# DEMO.net
KiCad netlist of a schematic drawn in Altium Designer
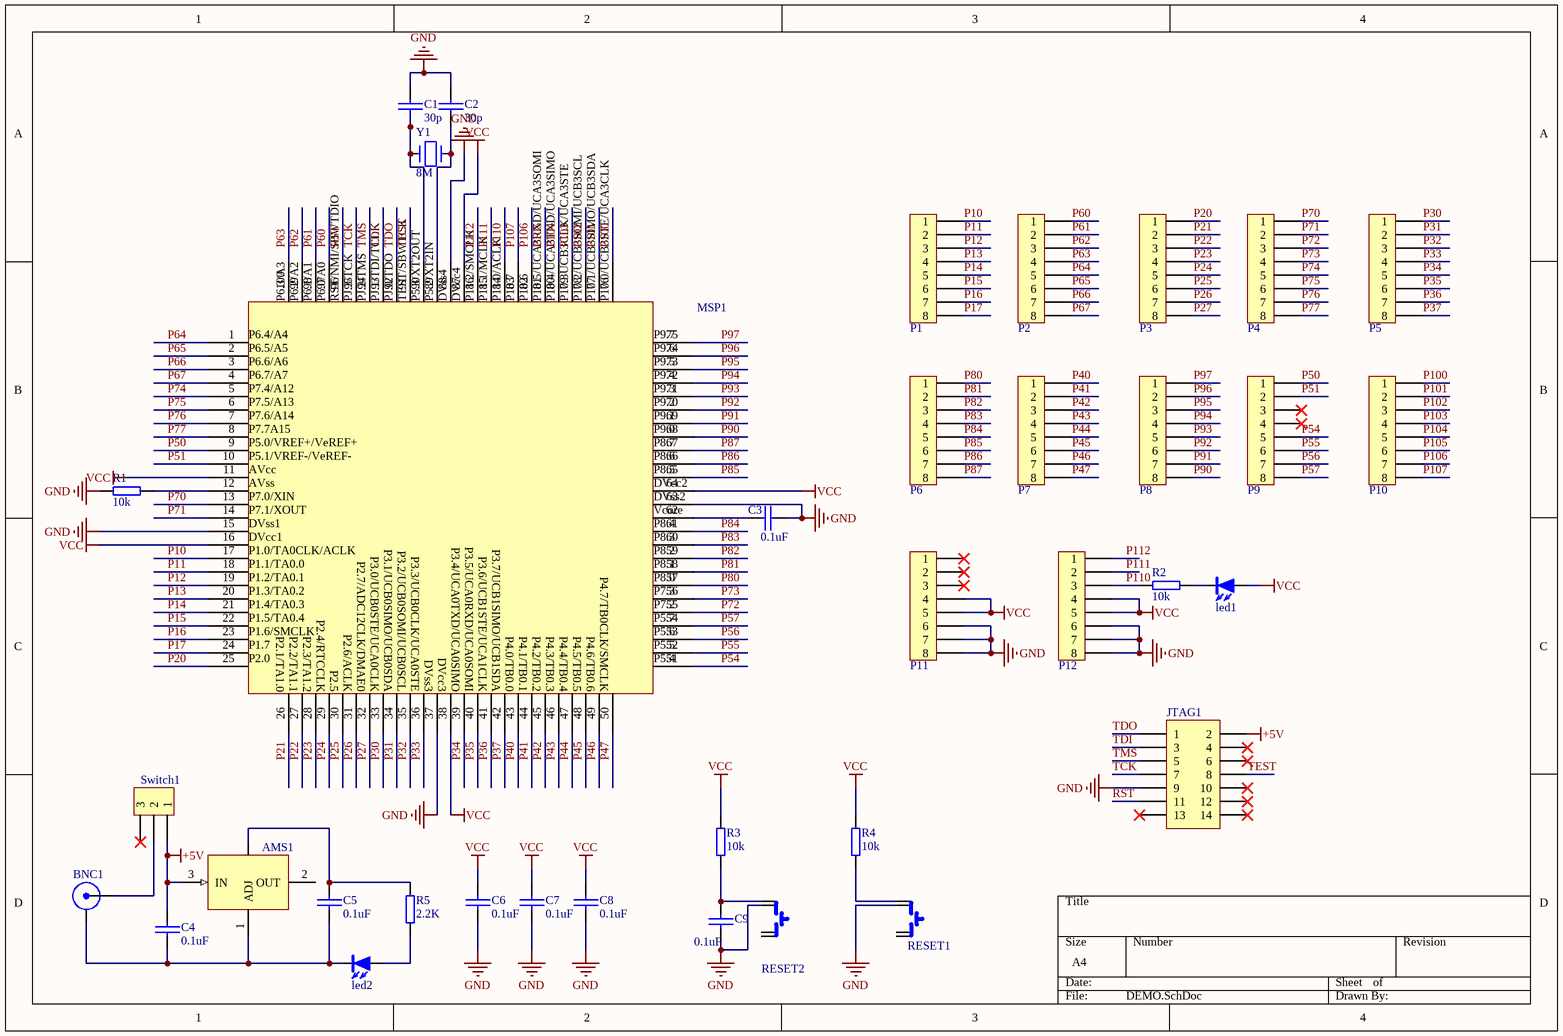
[diagram p0: DEMO.SchDoc]

(export (version "E")
  (design (tool "Eeschema 10.0.6"))
  (components
    (comp (ref "AMS1")
      (value "1117")
      (footprint "SOT-223/P2.3")
      (libsource (lib "MSP430F5438A") (part "1117"))
    )
    (comp (ref "BNC1") (value "BNC") (footprint "POWER0") (libsource (lib "MSP430F5438A") (part "BNC")))
    (comp (ref "C1") (value "30p") (footprint "0805") (libsource (lib "MSP430F5438A") (part "C1")))
    (comp (ref "C2") (value "30p") (footprint "0805") (libsource (lib "MSP430F5438A") (part "C1")))
    (comp (ref "C3") (value "0.1uF") (footprint "0805") (libsource (lib "MSP430F5438A") (part "C1")))
    (comp (ref "C4") (value "0.1uF") (footprint "0805") (libsource (lib "MSP430F5438A") (part "C1")))
    (comp (ref "C5") (value "0.1uF") (footprint "0805") (libsource (lib "MSP430F5438A") (part "C1")))
    (comp (ref "C6") (value "0.1uF") (footprint "0805") (libsource (lib "MSP430F5438A") (part "C1")))
    (comp (ref "C7") (value "0.1uF") (footprint "0805") (libsource (lib "MSP430F5438A") (part "C1")))
    (comp (ref "C8") (value "0.1uF") (footprint "0805") (libsource (lib "MSP430F5438A") (part "C1")))
    (comp (ref "C9") (value "0.1uF") (footprint "0805") (libsource (lib "MSP430F5438A") (part "C1")))
    (comp (ref "JTAG1")
      (value "Header 7X2")
      (footprint "IDC14A")
      (description "Header, 7-Pin, Dual row")
      (fields (field (name "PUBLISHER") "Altium Limited"))
      (libsource (lib "MSP430F5438A") (part "Header 7X2"))
    )
    (comp (ref "led1") (value "LED2") (footprint "0805") (libsource (lib "MSP430F5438A") (part "LED2")))
    (comp (ref "led2") (value "LED2") (footprint "0805") (libsource (lib "MSP430F5438A") (part "LED2")))
    (comp (ref "MSP1")
      (value "MSP430F5438")
      (footprint "TQFP100")
      (libsource (lib "MSP430F5438A") (part "MSP430F5438"))
    )
    (comp (ref "P1") (value "CON8") (footprint "SIP8") (libsource (lib "MSP430F5438A") (part "CON8")))
    (comp (ref "P2") (value "CON8") (footprint "SIP8") (libsource (lib "MSP430F5438A") (part "CON8")))
    (comp (ref "P3") (value "CON8") (footprint "SIP8") (libsource (lib "MSP430F5438A") (part "CON8")))
    (comp (ref "P4") (value "CON8") (footprint "SIP8") (libsource (lib "MSP430F5438A") (part "CON8")))
    (comp (ref "P5") (value "CON8") (footprint "SIP8") (libsource (lib "MSP430F5438A") (part "CON8")))
    (comp (ref "P6") (value "CON8") (footprint "SIP8") (libsource (lib "MSP430F5438A") (part "CON8")))
    (comp (ref "P7") (value "CON8") (footprint "SIP8") (libsource (lib "MSP430F5438A") (part "CON8")))
    (comp (ref "P8") (value "CON8") (footprint "SIP8") (libsource (lib "MSP430F5438A") (part "CON8")))
    (comp (ref "P9") (value "CON8") (footprint "SIP8") (libsource (lib "MSP430F5438A") (part "CON8")))
    (comp (ref "P10") (value "CON8") (footprint "SIP8") (libsource (lib "MSP430F5438A") (part "CON8")))
    (comp (ref "P11") (value "CON8") (footprint "SIP8") (libsource (lib "MSP430F5438A") (part "CON8")))
    (comp (ref "P12") (value "CON8") (footprint "SIP8") (libsource (lib "MSP430F5438A") (part "CON8")))
    (comp (ref "R1") (value "10k") (footprint "0805") (libsource (lib "MSP430F5438A") (part "R1")))
    (comp (ref "R2") (value "10k") (footprint "0805") (libsource (lib "MSP430F5438A") (part "R1")))
    (comp (ref "R3") (value "10k") (footprint "0805") (libsource (lib "MSP430F5438A") (part "R1")))
    (comp (ref "R4") (value "10k") (footprint "0805") (libsource (lib "MSP430F5438A") (part "R1")))
    (comp (ref "R5") (value "2.2K") (footprint "0805") (libsource (lib "MSP430F5438A") (part "R1")))
    (comp (ref "RESET1") (value "KEY2") (footprint "KEY0.2'") (libsource (lib "MSP430F5438A") (part "KEY2")))
    (comp (ref "RESET2") (value "KEY2") (footprint "KEY0.2'") (libsource (lib "MSP430F5438A") (part "KEY2")))
    (comp (ref "Switch1") (value "CON3") (footprint "5脚船型开关") (libsource (lib "MSP430F5438A") (part "CON3")))
    (comp (ref "Y1") (value "8M") (footprint "CY1") (libsource (lib "MSP430F5438A") (part "CY1")))
  )
  (nets
    (net (code "1") (name "+5V") (class "Default")
      (node (ref "AMS1") (pin "3") (pinfunction "IN_3") (pintype "input"))
      (node (ref "C4") (pin "1") (pinfunction "1_1") (pintype "passive"))
      (node (ref "JTAG1") (pin "2") (pinfunction "2_2") (pintype "passive"))
      (node (ref "Switch1") (pin "1") (pinfunction "1_1") (pintype "passive"))
    )
    (net (code "2") (name "/P10") (class "Default")
      (node (ref "MSP1") (pin "17") (pinfunction "17_17") (pintype "passive"))
      (node (ref "P1") (pin "1") (pinfunction "1_1") (pintype "passive"))
    )
    (net (code "3") (name "/P11") (class "Default")
      (node (ref "MSP1") (pin "18") (pinfunction "18_18") (pintype "passive"))
      (node (ref "P1") (pin "2") (pinfunction "2_2") (pintype "passive"))
    )
    (net (code "4") (name "/P12") (class "Default")
      (node (ref "MSP1") (pin "19") (pinfunction "19_19") (pintype "passive"))
      (node (ref "P1") (pin "3") (pinfunction "3_3") (pintype "passive"))
    )
    (net (code "5") (name "/P13") (class "Default")
      (node (ref "MSP1") (pin "20") (pinfunction "20_20") (pintype "passive"))
      (node (ref "P1") (pin "4") (pinfunction "4_4") (pintype "passive"))
    )
    (net (code "6") (name "/P14") (class "Default")
      (node (ref "MSP1") (pin "21") (pinfunction "21_21") (pintype "passive"))
      (node (ref "P1") (pin "5") (pinfunction "5_5") (pintype "passive"))
    )
    (net (code "7") (name "/P15") (class "Default")
      (node (ref "MSP1") (pin "22") (pinfunction "22_22") (pintype "passive"))
      (node (ref "P1") (pin "6") (pinfunction "6_6") (pintype "passive"))
    )
    (net (code "8") (name "/P16") (class "Default")
      (node (ref "MSP1") (pin "23") (pinfunction "23_23") (pintype "passive"))
      (node (ref "P1") (pin "7") (pinfunction "7_7") (pintype "passive"))
    )
    (net (code "9") (name "/P17") (class "Default")
      (node (ref "MSP1") (pin "24") (pinfunction "24_24") (pintype "passive"))
      (node (ref "P1") (pin "8") (pinfunction "8_8") (pintype "passive"))
    )
    (net (code "10") (name "/P20") (class "Default")
      (node (ref "MSP1") (pin "25") (pinfunction "25_25") (pintype "passive"))
      (node (ref "P3") (pin "1") (pinfunction "1_1") (pintype "passive"))
    )
    (net (code "11") (name "/P21") (class "Default")
      (node (ref "MSP1") (pin "26") (pinfunction "26_26") (pintype "passive"))
      (node (ref "P3") (pin "2") (pinfunction "2_2") (pintype "passive"))
    )
    (net (code "12") (name "/P22") (class "Default")
      (node (ref "MSP1") (pin "27") (pinfunction "27_27") (pintype "passive"))
      (node (ref "P3") (pin "3") (pinfunction "3_3") (pintype "passive"))
    )
    (net (code "13") (name "/P23") (class "Default")
      (node (ref "MSP1") (pin "28") (pinfunction "28_28") (pintype "passive"))
      (node (ref "P3") (pin "4") (pinfunction "4_4") (pintype "passive"))
    )
    (net (code "14") (name "/P24") (class "Default")
      (node (ref "MSP1") (pin "29") (pinfunction "29_29") (pintype "passive"))
      (node (ref "P3") (pin "5") (pinfunction "5_5") (pintype "passive"))
    )
    (net (code "15") (name "/P25") (class "Default")
      (node (ref "MSP1") (pin "30") (pinfunction "30_30") (pintype "passive"))
      (node (ref "P3") (pin "6") (pinfunction "6_6") (pintype "passive"))
    )
    (net (code "16") (name "/P26") (class "Default")
      (node (ref "MSP1") (pin "31") (pinfunction "31_31") (pintype "passive"))
      (node (ref "P3") (pin "7") (pinfunction "7_7") (pintype "passive"))
    )
    (net (code "17") (name "/P27") (class "Default")
      (node (ref "MSP1") (pin "32") (pinfunction "32_32") (pintype "passive"))
      (node (ref "P3") (pin "8") (pinfunction "8_8") (pintype "passive"))
    )
    (net (code "18") (name "/P30") (class "Default")
      (node (ref "MSP1") (pin "33") (pinfunction "33_33") (pintype "passive"))
      (node (ref "P5") (pin "1") (pinfunction "1_1") (pintype "passive"))
    )
    (net (code "19") (name "/P31") (class "Default")
      (node (ref "MSP1") (pin "34") (pinfunction "34_34") (pintype "passive"))
      (node (ref "P5") (pin "2") (pinfunction "2_2") (pintype "passive"))
    )
    (net (code "20") (name "/P32") (class "Default")
      (node (ref "MSP1") (pin "35") (pinfunction "35_35") (pintype "passive"))
      (node (ref "P5") (pin "3") (pinfunction "3_3") (pintype "passive"))
    )
    (net (code "21") (name "/P33") (class "Default")
      (node (ref "MSP1") (pin "36") (pinfunction "36_36") (pintype "passive"))
      (node (ref "P5") (pin "4") (pinfunction "4_4") (pintype "passive"))
    )
    (net (code "22") (name "/P34") (class "Default")
      (node (ref "MSP1") (pin "39") (pinfunction "39_39") (pintype "passive"))
      (node (ref "P5") (pin "5") (pinfunction "5_5") (pintype "passive"))
    )
    (net (code "23") (name "/P35") (class "Default")
      (node (ref "MSP1") (pin "40") (pinfunction "40_40") (pintype "passive"))
      (node (ref "P5") (pin "6") (pinfunction "6_6") (pintype "passive"))
    )
    (net (code "24") (name "/P36") (class "Default")
      (node (ref "MSP1") (pin "41") (pinfunction "41_41") (pintype "passive"))
      (node (ref "P5") (pin "7") (pinfunction "7_7") (pintype "passive"))
    )
    (net (code "25") (name "/P37") (class "Default")
      (node (ref "MSP1") (pin "42") (pinfunction "42_42") (pintype "passive"))
      (node (ref "P5") (pin "8") (pinfunction "8_8") (pintype "passive"))
    )
    (net (code "26") (name "/P40") (class "Default")
      (node (ref "MSP1") (pin "43") (pinfunction "43_43") (pintype "passive"))
      (node (ref "P7") (pin "1") (pinfunction "1_1") (pintype "passive"))
    )
    (net (code "27") (name "/P41") (class "Default")
      (node (ref "MSP1") (pin "44") (pinfunction "44_44") (pintype "passive"))
      (node (ref "P7") (pin "2") (pinfunction "2_2") (pintype "passive"))
    )
    (net (code "28") (name "/P42") (class "Default")
      (node (ref "MSP1") (pin "45") (pinfunction "45_45") (pintype "passive"))
      (node (ref "P7") (pin "3") (pinfunction "3_3") (pintype "passive"))
    )
    (net (code "29") (name "/P43") (class "Default")
      (node (ref "MSP1") (pin "46") (pinfunction "46_46") (pintype "passive"))
      (node (ref "P7") (pin "4") (pinfunction "4_4") (pintype "passive"))
    )
    (net (code "30") (name "/P44") (class "Default")
      (node (ref "MSP1") (pin "47") (pinfunction "47_47") (pintype "passive"))
      (node (ref "P7") (pin "5") (pinfunction "5_5") (pintype "passive"))
    )
    (net (code "31") (name "/P45") (class "Default")
      (node (ref "MSP1") (pin "48") (pinfunction "48_48") (pintype "passive"))
      (node (ref "P7") (pin "6") (pinfunction "6_6") (pintype "passive"))
    )
    (net (code "32") (name "/P46") (class "Default")
      (node (ref "MSP1") (pin "49") (pinfunction "49_49") (pintype "passive"))
      (node (ref "P7") (pin "7") (pinfunction "7_7") (pintype "passive"))
    )
    (net (code "33") (name "/P47") (class "Default")
      (node (ref "MSP1") (pin "50") (pinfunction "50_50") (pintype "passive"))
      (node (ref "P7") (pin "8") (pinfunction "8_8") (pintype "passive"))
    )
    (net (code "34") (name "/P50") (class "Default")
      (node (ref "MSP1") (pin "9") (pinfunction "9_9") (pintype "passive"))
      (node (ref "P9") (pin "1") (pinfunction "1_1") (pintype "passive"))
    )
    (net (code "35") (name "/P51") (class "Default")
      (node (ref "MSP1") (pin "10") (pinfunction "10_10") (pintype "passive"))
      (node (ref "P9") (pin "2") (pinfunction "2_2") (pintype "passive"))
    )
    (net (code "36") (name "/P54") (class "Default")
      (node (ref "MSP1") (pin "51") (pinfunction "51_51") (pintype "passive"))
      (node (ref "P9") (pin "5") (pinfunction "5_5") (pintype "passive"))
    )
    (net (code "37") (name "/P55") (class "Default")
      (node (ref "MSP1") (pin "52") (pinfunction "52_52") (pintype "passive"))
      (node (ref "P9") (pin "6") (pinfunction "6_6") (pintype "passive"))
    )
    (net (code "38") (name "/P56") (class "Default")
      (node (ref "MSP1") (pin "53") (pinfunction "53_53") (pintype "passive"))
      (node (ref "P9") (pin "7") (pinfunction "7_7") (pintype "passive"))
    )
    (net (code "39") (name "/P57") (class "Default")
      (node (ref "MSP1") (pin "54") (pinfunction "54_54") (pintype "passive"))
      (node (ref "P9") (pin "8") (pinfunction "8_8") (pintype "passive"))
    )
    (net (code "40") (name "/P60") (class "Default")
      (node (ref "MSP1") (pin "97") (pinfunction "97_97") (pintype "passive"))
      (node (ref "P2") (pin "1") (pinfunction "1_1") (pintype "passive"))
    )
    (net (code "41") (name "/P61") (class "Default")
      (node (ref "MSP1") (pin "98") (pinfunction "98_98") (pintype "passive"))
      (node (ref "P2") (pin "2") (pinfunction "2_2") (pintype "passive"))
    )
    (net (code "42") (name "/P62") (class "Default")
      (node (ref "MSP1") (pin "99") (pinfunction "99_99") (pintype "passive"))
      (node (ref "P2") (pin "3") (pinfunction "3_3") (pintype "passive"))
    )
    (net (code "43") (name "/P63") (class "Default")
      (node (ref "MSP1") (pin "100") (pinfunction "100_100") (pintype "passive"))
      (node (ref "P2") (pin "4") (pinfunction "4_4") (pintype "passive"))
    )
    (net (code "44") (name "/P64") (class "Default")
      (node (ref "MSP1") (pin "1") (pinfunction "1_1") (pintype "passive"))
      (node (ref "P2") (pin "5") (pinfunction "5_5") (pintype "passive"))
    )
    (net (code "45") (name "/P65") (class "Default")
      (node (ref "MSP1") (pin "2") (pinfunction "2_2") (pintype "passive"))
      (node (ref "P2") (pin "6") (pinfunction "6_6") (pintype "passive"))
    )
    (net (code "46") (name "/P66") (class "Default")
      (node (ref "MSP1") (pin "3") (pinfunction "3_3") (pintype "passive"))
      (node (ref "P2") (pin "7") (pinfunction "7_7") (pintype "passive"))
    )
    (net (code "47") (name "/P67") (class "Default")
      (node (ref "MSP1") (pin "4") (pinfunction "4_4") (pintype "passive"))
      (node (ref "P2") (pin "8") (pinfunction "8_8") (pintype "passive"))
    )
    (net (code "48") (name "/P70") (class "Default")
      (node (ref "MSP1") (pin "13") (pinfunction "13_13") (pintype "passive"))
      (node (ref "P4") (pin "1") (pinfunction "1_1") (pintype "passive"))
    )
    (net (code "49") (name "/P71") (class "Default")
      (node (ref "MSP1") (pin "14") (pinfunction "14_14") (pintype "passive"))
      (node (ref "P4") (pin "2") (pinfunction "2_2") (pintype "passive"))
    )
    (net (code "50") (name "/P72") (class "Default")
      (node (ref "MSP1") (pin "55") (pinfunction "55_55") (pintype "passive"))
      (node (ref "P4") (pin "3") (pinfunction "3_3") (pintype "passive"))
    )
    (net (code "51") (name "/P73") (class "Default")
      (node (ref "MSP1") (pin "56") (pinfunction "56_56") (pintype "passive"))
      (node (ref "P4") (pin "4") (pinfunction "4_4") (pintype "passive"))
    )
    (net (code "52") (name "/P74") (class "Default")
      (node (ref "MSP1") (pin "5") (pinfunction "5_5") (pintype "passive"))
      (node (ref "P4") (pin "5") (pinfunction "5_5") (pintype "passive"))
    )
    (net (code "53") (name "/P75") (class "Default")
      (node (ref "MSP1") (pin "6") (pinfunction "6_6") (pintype "passive"))
      (node (ref "P4") (pin "6") (pinfunction "6_6") (pintype "passive"))
    )
    (net (code "54") (name "/P76") (class "Default")
      (node (ref "MSP1") (pin "7") (pinfunction "7_7") (pintype "passive"))
      (node (ref "P4") (pin "7") (pinfunction "7_7") (pintype "passive"))
    )
    (net (code "55") (name "/P77") (class "Default")
      (node (ref "MSP1") (pin "8") (pinfunction "8_8") (pintype "passive"))
      (node (ref "P4") (pin "8") (pinfunction "8_8") (pintype "passive"))
    )
    (net (code "56") (name "/P80") (class "Default")
      (node (ref "MSP1") (pin "57") (pinfunction "57_57") (pintype "passive"))
      (node (ref "P6") (pin "1") (pinfunction "1_1") (pintype "passive"))
    )
    (net (code "57") (name "/P81") (class "Default")
      (node (ref "MSP1") (pin "58") (pinfunction "58_58") (pintype "passive"))
      (node (ref "P6") (pin "2") (pinfunction "2_2") (pintype "passive"))
    )
    (net (code "58") (name "/P82") (class "Default")
      (node (ref "MSP1") (pin "59") (pinfunction "59_59") (pintype "passive"))
      (node (ref "P6") (pin "3") (pinfunction "3_3") (pintype "passive"))
    )
    (net (code "59") (name "/P83") (class "Default")
      (node (ref "MSP1") (pin "60") (pinfunction "60_60") (pintype "passive"))
      (node (ref "P6") (pin "4") (pinfunction "4_4") (pintype "passive"))
    )
    (net (code "60") (name "/P84") (class "Default")
      (node (ref "MSP1") (pin "61") (pinfunction "61_61") (pintype "passive"))
      (node (ref "P6") (pin "5") (pinfunction "5_5") (pintype "passive"))
    )
    (net (code "61") (name "/P85") (class "Default")
      (node (ref "MSP1") (pin "65") (pinfunction "65_65") (pintype "passive"))
      (node (ref "P6") (pin "6") (pinfunction "6_6") (pintype "passive"))
    )
    (net (code "62") (name "/P86") (class "Default")
      (node (ref "MSP1") (pin "66") (pinfunction "66_66") (pintype "passive"))
      (node (ref "P6") (pin "7") (pinfunction "7_7") (pintype "passive"))
    )
    (net (code "63") (name "/P87") (class "Default")
      (node (ref "MSP1") (pin "67") (pinfunction "67_67") (pintype "passive"))
      (node (ref "P6") (pin "8") (pinfunction "8_8") (pintype "passive"))
    )
    (net (code "64") (name "/P90") (class "Default")
      (node (ref "MSP1") (pin "68") (pinfunction "68_68") (pintype "passive"))
      (node (ref "P8") (pin "8") (pinfunction "8_8") (pintype "passive"))
    )
    (net (code "65") (name "/P91") (class "Default")
      (node (ref "MSP1") (pin "69") (pinfunction "69_69") (pintype "passive"))
      (node (ref "P8") (pin "7") (pinfunction "7_7") (pintype "passive"))
    )
    (net (code "66") (name "/P92") (class "Default")
      (node (ref "MSP1") (pin "70") (pinfunction "70_70") (pintype "passive"))
      (node (ref "P8") (pin "6") (pinfunction "6_6") (pintype "passive"))
    )
    (net (code "67") (name "/P93") (class "Default")
      (node (ref "MSP1") (pin "71") (pinfunction "71_71") (pintype "passive"))
      (node (ref "P8") (pin "5") (pinfunction "5_5") (pintype "passive"))
    )
    (net (code "68") (name "/P94") (class "Default")
      (node (ref "MSP1") (pin "72") (pinfunction "72_72") (pintype "passive"))
      (node (ref "P8") (pin "4") (pinfunction "4_4") (pintype "passive"))
    )
    (net (code "69") (name "/P95") (class "Default")
      (node (ref "MSP1") (pin "73") (pinfunction "73_73") (pintype "passive"))
      (node (ref "P8") (pin "3") (pinfunction "3_3") (pintype "passive"))
    )
    (net (code "70") (name "/P96") (class "Default")
      (node (ref "MSP1") (pin "74") (pinfunction "74_74") (pintype "passive"))
      (node (ref "P8") (pin "2") (pinfunction "2_2") (pintype "passive"))
    )
    (net (code "71") (name "/P97") (class "Default")
      (node (ref "MSP1") (pin "75") (pinfunction "75_75") (pintype "passive"))
      (node (ref "P8") (pin "1") (pinfunction "1_1") (pintype "passive"))
    )
    (net (code "72") (name "/P100") (class "Default")
      (node (ref "MSP1") (pin "76") (pinfunction "76_76") (pintype "passive"))
      (node (ref "P10") (pin "1") (pinfunction "1_1") (pintype "passive"))
    )
    (net (code "73") (name "/P101") (class "Default")
      (node (ref "MSP1") (pin "77") (pinfunction "77_77") (pintype "passive"))
      (node (ref "P10") (pin "2") (pinfunction "2_2") (pintype "passive"))
    )
    (net (code "74") (name "/P102") (class "Default")
      (node (ref "MSP1") (pin "78") (pinfunction "78_78") (pintype "passive"))
      (node (ref "P10") (pin "3") (pinfunction "3_3") (pintype "passive"))
    )
    (net (code "75") (name "/P103") (class "Default")
      (node (ref "MSP1") (pin "79") (pinfunction "79_79") (pintype "passive"))
      (node (ref "P10") (pin "4") (pinfunction "4_4") (pintype "passive"))
    )
    (net (code "76") (name "/P104") (class "Default")
      (node (ref "MSP1") (pin "80") (pinfunction "80_80") (pintype "passive"))
      (node (ref "P10") (pin "5") (pinfunction "5_5") (pintype "passive"))
    )
    (net (code "77") (name "/P105") (class "Default")
      (node (ref "MSP1") (pin "81") (pinfunction "81_81") (pintype "passive"))
      (node (ref "P10") (pin "6") (pinfunction "6_6") (pintype "passive"))
    )
    (net (code "78") (name "/P106") (class "Default")
      (node (ref "MSP1") (pin "82") (pinfunction "82_82") (pintype "passive"))
      (node (ref "P10") (pin "7") (pinfunction "7_7") (pintype "passive"))
    )
    (net (code "79") (name "/P107") (class "Default")
      (node (ref "MSP1") (pin "83") (pinfunction "83_83") (pintype "passive"))
      (node (ref "P10") (pin "8") (pinfunction "8_8") (pintype "passive"))
    )
    (net (code "80") (name "/P110") (class "Default")
      (node (ref "MSP1") (pin "84") (pinfunction "84_84") (pintype "passive"))
      (node (ref "P12") (pin "3") (pinfunction "3_3") (pintype "passive"))
      (node (ref "R2") (pin "1") (pinfunction "1_1") (pintype "passive"))
    )
    (net (code "81") (name "/P111") (class "Default")
      (node (ref "MSP1") (pin "85") (pinfunction "85_85") (pintype "passive"))
      (node (ref "P12") (pin "2") (pinfunction "2_2") (pintype "passive"))
    )
    (net (code "82") (name "/P112") (class "Default")
      (node (ref "MSP1") (pin "86") (pinfunction "86_86") (pintype "passive"))
      (node (ref "P12") (pin "1") (pinfunction "1_1") (pintype "passive"))
    )
    (net (code "83") (name "/RST") (class "Default")
      (node (ref "JTAG1") (pin "11") (pinfunction "11_11") (pintype "passive"))
      (node (ref "MSP1") (pin "96") (pinfunction "96_96") (pintype "passive"))
    )
    (net (code "84") (name "/TCK") (class "Default")
      (node (ref "JTAG1") (pin "7") (pinfunction "7_7") (pintype "passive"))
      (node (ref "MSP1") (pin "95") (pinfunction "95_95") (pintype "passive"))
    )
    (net (code "85") (name "/TDI") (class "Default")
      (node (ref "JTAG1") (pin "3") (pinfunction "3_3") (pintype "passive"))
      (node (ref "MSP1") (pin "93") (pinfunction "93_93") (pintype "passive"))
    )
    (net (code "86") (name "/TDO") (class "Default")
      (node (ref "JTAG1") (pin "1") (pinfunction "1_1") (pintype "passive"))
      (node (ref "MSP1") (pin "92") (pinfunction "92_92") (pintype "passive"))
    )
    (net (code "87") (name "/TEST") (class "Default")
      (node (ref "JTAG1") (pin "8") (pinfunction "8_8") (pintype "passive"))
      (node (ref "MSP1") (pin "91") (pinfunction "91_91") (pintype "passive"))
    )
    (net (code "88") (name "/TMS") (class "Default")
      (node (ref "JTAG1") (pin "5") (pinfunction "5_5") (pintype "passive"))
      (node (ref "MSP1") (pin "94") (pinfunction "94_94") (pintype "passive"))
    )
    (net (code "89") (name "GND") (class "Default")
      (node (ref "C1") (pin "1") (pinfunction "1_1") (pintype "passive"))
      (node (ref "C2") (pin "1") (pinfunction "1_1") (pintype "passive"))
      (node (ref "C3") (pin "1") (pinfunction "1_1") (pintype "passive"))
      (node (ref "C6") (pin "2") (pinfunction "2_2") (pintype "passive"))
      (node (ref "C7") (pin "2") (pinfunction "2_2") (pintype "passive"))
      (node (ref "C8") (pin "2") (pinfunction "2_2") (pintype "passive"))
      (node (ref "C9") (pin "2") (pinfunction "2_2") (pintype "passive"))
      (node (ref "JTAG1") (pin "9") (pinfunction "9_9") (pintype "passive"))
      (node (ref "MSP1") (pin "15") (pinfunction "15_15") (pintype "passive"))
      (node (ref "MSP1") (pin "37") (pinfunction "37_37") (pintype "passive"))
      (node (ref "MSP1") (pin "63") (pinfunction "63_63") (pintype "passive"))
      (node (ref "MSP1") (pin "88") (pinfunction "88_88") (pintype "passive"))
      (node (ref "P11") (pin "6") (pinfunction "6_6") (pintype "passive"))
      (node (ref "P11") (pin "7") (pinfunction "7_7") (pintype "passive"))
      (node (ref "P11") (pin "8") (pinfunction "8_8") (pintype "passive"))
      (node (ref "P12") (pin "6") (pinfunction "6_6") (pintype "passive"))
      (node (ref "P12") (pin "7") (pinfunction "7_7") (pintype "passive"))
      (node (ref "P12") (pin "8") (pinfunction "8_8") (pintype "passive"))
      (node (ref "R1") (pin "1") (pinfunction "1_1") (pintype "passive"))
      (node (ref "RESET1") (pin "4") (pintype "passive"))
      (node (ref "RESET2") (pin "4") (pintype "passive"))
    )
    (net (code "90") (name "Net-(AMS1-ADJ)") (class "Default")
      (node (ref "AMS1") (pin "1") (pinfunction "ADJ_1") (pintype "power_in"))
      (node (ref "BNC1") (pin "2") (pinfunction "2_2") (pintype "passive"))
      (node (ref "C4") (pin "2") (pinfunction "2_2") (pintype "passive"))
      (node (ref "C5") (pin "2") (pinfunction "2_2") (pintype "passive"))
      (node (ref "led2") (pin "2") (pinfunction "2_2") (pintype "passive"))
    )
    (net (code "91") (name "Net-(AMS1-Pad4)") (class "Default")
      (node (ref "AMS1") (pin "4") (pintype "passive"))
      (node (ref "C5") (pin "1") (pinfunction "1_1") (pintype "passive"))
      (node (ref "R5") (pin "2") (pinfunction "2_2") (pintype "passive"))
    )
    (net (code "92") (name "Net-(BNC1-Pad1)") (class "Default")
      (node (ref "BNC1") (pin "1") (pinfunction "1_1") (pintype "passive"))
      (node (ref "Switch1") (pin "2") (pinfunction "2_2") (pintype "passive"))
    )
    (net (code "93") (name "Net-(C1-Pad2)") (class "Default")
      (node (ref "C1") (pin "2") (pinfunction "2_2") (pintype "passive"))
      (node (ref "MSP1") (pin "90") (pinfunction "90_90") (pintype "passive"))
      (node (ref "Y1") (pin "1") (pinfunction "1_1") (pintype "passive"))
    )
    (net (code "94") (name "Net-(C2-Pad2)") (class "Default")
      (node (ref "C2") (pin "2") (pinfunction "2_2") (pintype "passive"))
      (node (ref "MSP1") (pin "89") (pinfunction "89_89") (pintype "passive"))
      (node (ref "Y1") (pin "2") (pinfunction "2_2") (pintype "passive"))
    )
    (net (code "95") (name "Net-(C3-Pad2)") (class "Default")
      (node (ref "C3") (pin "2") (pinfunction "2_2") (pintype "passive"))
      (node (ref "MSP1") (pin "62") (pinfunction "62_62") (pintype "passive"))
    )
    (net (code "96") (name "Net-(C9-Pad1)") (class "Default")
      (node (ref "C9") (pin "1") (pinfunction "1_1") (pintype "passive"))
      (node (ref "R3") (pin "1") (pinfunction "1_1") (pintype "passive"))
      (node (ref "RESET2") (pin "3") (pintype "passive"))
    )
    (net (code "97") (name "Net-(MSP1-Pad12)") (class "Default")
      (node (ref "MSP1") (pin "12") (pinfunction "12_12") (pintype "passive"))
      (node (ref "R1") (pin "2") (pinfunction "2_2") (pintype "passive"))
    )
    (net (code "98") (name "Net-(R2-Pad2)") (class "Default")
      (node (ref "R2") (pin "2") (pinfunction "2_2") (pintype "passive"))
      (node (ref "led1") (pin "2") (pinfunction "2_2") (pintype "passive"))
    )
    (net (code "99") (name "Net-(R4-Pad1)") (class "Default")
      (node (ref "R4") (pin "1") (pinfunction "1_1") (pintype "passive"))
      (node (ref "RESET1") (pin "3") (pintype "passive"))
    )
    (net (code "100") (name "Net-(R5-Pad1)") (class "Default")
      (node (ref "R5") (pin "1") (pinfunction "1_1") (pintype "passive"))
      (node (ref "led2") (pin "1") (pinfunction "1_1") (pintype "passive"))
    )
    (net (code "101") (name "VCC") (class "Default")
      (node (ref "C6") (pin "1") (pinfunction "1_1") (pintype "passive"))
      (node (ref "C7") (pin "1") (pinfunction "1_1") (pintype "passive"))
      (node (ref "C8") (pin "1") (pinfunction "1_1") (pintype "passive"))
      (node (ref "MSP1") (pin "11") (pinfunction "11_11") (pintype "passive"))
      (node (ref "MSP1") (pin "16") (pinfunction "16_16") (pintype "passive"))
      (node (ref "MSP1") (pin "38") (pinfunction "38_38") (pintype "passive"))
      (node (ref "MSP1") (pin "64") (pinfunction "64_64") (pintype "passive"))
      (node (ref "MSP1") (pin "87") (pinfunction "87_87") (pintype "passive"))
      (node (ref "P11") (pin "4") (pinfunction "4_4") (pintype "passive"))
      (node (ref "P11") (pin "5") (pinfunction "5_5") (pintype "passive"))
      (node (ref "P12") (pin "4") (pinfunction "4_4") (pintype "passive"))
      (node (ref "P12") (pin "5") (pinfunction "5_5") (pintype "passive"))
      (node (ref "R3") (pin "2") (pinfunction "2_2") (pintype "passive"))
      (node (ref "R4") (pin "2") (pinfunction "2_2") (pintype "passive"))
      (node (ref "led1") (pin "1") (pinfunction "1_1") (pintype "passive"))
    )
    (net (code "102") (name "unconnected-(AMS1-OUT-Pad2)") (class "Default")
      (node (ref "AMS1") (pin "2") (pinfunction "OUT_2") (pintype "power_in"))
    )
    (net (code "103") (name "unconnected-(JTAG1-Pad4)") (class "Default")
      (node (ref "JTAG1") (pin "4") (pinfunction "4_4") (pintype "passive+no_connect"))
    )
    (net (code "104") (name "unconnected-(JTAG1-Pad6)") (class "Default")
      (node (ref "JTAG1") (pin "6") (pinfunction "6_6") (pintype "passive+no_connect"))
    )
    (net (code "105") (name "unconnected-(JTAG1-Pad10)") (class "Default")
      (node (ref "JTAG1") (pin "10") (pinfunction "10_10") (pintype "passive+no_connect"))
    )
    (net (code "106") (name "unconnected-(JTAG1-Pad12)") (class "Default")
      (node (ref "JTAG1") (pin "12") (pinfunction "12_12") (pintype "passive+no_connect"))
    )
    (net (code "107") (name "unconnected-(JTAG1-Pad13)") (class "Default")
      (node (ref "JTAG1") (pin "13") (pinfunction "13_13") (pintype "passive+no_connect"))
    )
    (net (code "108") (name "unconnected-(JTAG1-Pad14)") (class "Default")
      (node (ref "JTAG1") (pin "14") (pinfunction "14_14") (pintype "passive+no_connect"))
    )
    (net (code "109") (name "unconnected-(P9-Pad3)") (class "Default")
      (node (ref "P9") (pin "3") (pinfunction "3_3") (pintype "passive+no_connect"))
    )
    (net (code "110") (name "unconnected-(P9-Pad4)") (class "Default")
      (node (ref "P9") (pin "4") (pinfunction "4_4") (pintype "passive+no_connect"))
    )
    (net (code "111") (name "unconnected-(P11-Pad1)") (class "Default")
      (node (ref "P11") (pin "1") (pinfunction "1_1") (pintype "passive+no_connect"))
    )
    (net (code "112") (name "unconnected-(P11-Pad2)") (class "Default")
      (node (ref "P11") (pin "2") (pinfunction "2_2") (pintype "passive+no_connect"))
    )
    (net (code "113") (name "unconnected-(P11-Pad3)") (class "Default")
      (node (ref "P11") (pin "3") (pinfunction "3_3") (pintype "passive+no_connect"))
    )
    (net (code "114") (name "unconnected-(RESET1-Pad1)") (class "Default")
      (node (ref "RESET1") (pin "1") (pintype "passive"))
    )
    (net (code "115") (name "unconnected-(RESET1-Pad2)") (class "Default")
      (node (ref "RESET1") (pin "2") (pintype "passive"))
    )
    (net (code "116") (name "unconnected-(RESET2-Pad1)") (class "Default")
      (node (ref "RESET2") (pin "1") (pintype "passive"))
    )
    (net (code "117") (name "unconnected-(RESET2-Pad2)") (class "Default")
      (node (ref "RESET2") (pin "2") (pintype "passive"))
    )
    (net (code "118") (name "unconnected-(Switch1-Pad3)") (class "Default")
      (node (ref "Switch1") (pin "3") (pinfunction "3_3") (pintype "passive+no_connect"))
    )
  )
)
